# V4-AddOnSduino-V02-008.net
KiCad netlist of a schematic drawn in EAGLE
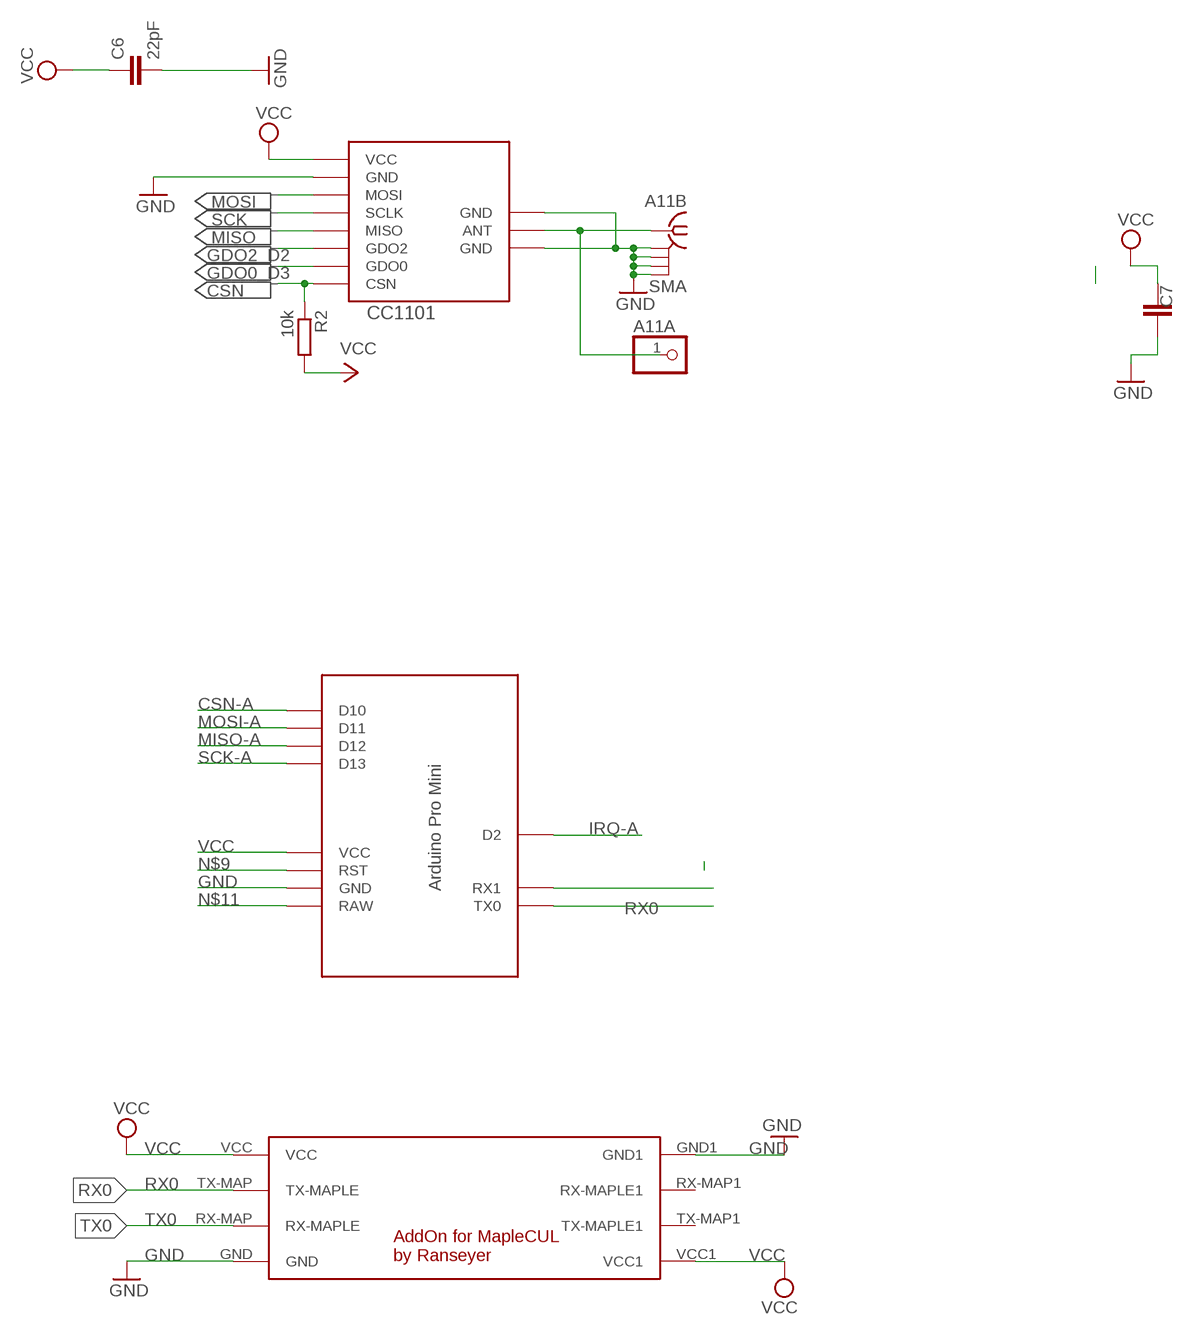
[diagram p0: schematic, sheet 1]

(export (version "E")
  (design (tool "Eeschema 10.0.6"))
  (components
    (comp (ref "A11A")
      (value "PINHD-1X1")
      (footprint "eagle-import:1X01")
      (libsource (lib "eagle-import") (part "PINHD-1X1"))
    )
    (comp (ref "A11B")
      (value "SMA")
      (footprint "eagle-import:SMA")
      (libsource (lib "eagle-import") (part "SMA"))
    )
    (comp (ref "C6")
      (value "22pF")
      (footprint "eagle-import:C0805")
      (libsource (lib "eagle-import") (part "C-EUC0805"))
    )
    (comp (ref "C7")
      (value "C-EUC1812")
      (footprint "eagle-import:C1812")
      (libsource (lib "eagle-import") (part "C-EUC1812"))
    )
    (comp (ref "CC1101")
      (value "CC1101_MODULE1SMD")
      (footprint "eagle-import:CC1101_MODULE1_SMD")
      (libsource (lib "eagle-import") (part "CC1101_MODULE1SMD"))
    )
    (comp (ref "R2")
      (value "10k")
      (footprint "eagle-import:M0805")
      (libsource (lib "eagle-import") (part "R-EU_M0805"))
    )
    (comp (ref "U$1")
      (value "MARTIN-PROMINI-SPI")
      (footprint "eagle-import:MARTIN-PRO-SPI")
      (libsource (lib "eagle-import") (part "MARTIN-PROMINI-SPI"))
    )
    (comp (ref "U$2")
      (value "MAPLE-CUL-ADDON-V01")
      (footprint "eagle-import:MAPLE-CUL-V01")
      (libsource (lib "eagle-import") (part "MAPLE-CUL-ADDON-V01"))
    )
  )
  (nets
    (net (code "1") (name "/CSN") (class "Default")
      (node (ref "CC1101") (pin "CSN") (pinfunction "CSN_CSN") (pintype "bidirectional"))
      (node (ref "R2") (pin "1") (pinfunction "1_1") (pintype "passive"))
    )
    (net (code "2") (name "/CSN-A") (class "Default")
      (node (ref "U$1") (pin "D10") (pinfunction "D10_D10") (pintype "bidirectional"))
    )
    (net (code "3") (name "/GDO0_D3") (class "Default")
      (node (ref "CC1101") (pin "GDO0") (pinfunction "GDO0_GDO0") (pintype "bidirectional"))
    )
    (net (code "4") (name "/GDO2_D2") (class "Default")
      (node (ref "CC1101") (pin "GDO2") (pinfunction "GDO2_GDO2") (pintype "bidirectional"))
    )
    (net (code "5") (name "/IRQ-A") (class "Default")
      (node (ref "U$1") (pin "D2") (pinfunction "D2_D2") (pintype "bidirectional"))
    )
    (net (code "6") (name "/MISO") (class "Default")
      (node (ref "CC1101") (pin "MISO") (pinfunction "MISO_MISO") (pintype "bidirectional"))
    )
    (net (code "7") (name "/MISO-A") (class "Default")
      (node (ref "U$1") (pin "D12") (pinfunction "D12_D12") (pintype "bidirectional"))
    )
    (net (code "8") (name "/MOSI") (class "Default")
      (node (ref "CC1101") (pin "MOSI") (pinfunction "MOSI_MOSI") (pintype "bidirectional"))
    )
    (net (code "9") (name "/MOSI-A") (class "Default")
      (node (ref "U$1") (pin "D11") (pinfunction "D11_D11") (pintype "bidirectional"))
    )
    (net (code "10") (name "/N$9") (class "Default")
      (node (ref "U$1") (pin "RST") (pinfunction "RST_RST") (pintype "bidirectional"))
    )
    (net (code "11") (name "/N$11") (class "Default")
      (node (ref "U$1") (pin "RAW") (pinfunction "RAW_RAW") (pintype "bidirectional"))
    )
    (net (code "12") (name "/SCK") (class "Default")
      (node (ref "CC1101") (pin "SCLK") (pinfunction "SCLK_SCLK") (pintype "bidirectional"))
    )
    (net (code "13") (name "/SCK-A") (class "Default")
      (node (ref "U$1") (pin "D13") (pinfunction "D13_D13") (pintype "bidirectional"))
    )
    (net (code "14") (name "GND") (class "Default")
      (node (ref "A11B") (pin "GND@1") (pinfunction "2_GND@1") (pintype "passive"))
      (node (ref "A11B") (pin "GND@2") (pinfunction "3_GND@2") (pintype "passive"))
      (node (ref "A11B") (pin "GND@3") (pinfunction "4_GND@3") (pintype "passive"))
      (node (ref "A11B") (pin "GND@4") (pinfunction "5_GND@4") (pintype "passive"))
      (node (ref "C6") (pin "2") (pinfunction "2_2") (pintype "passive"))
      (node (ref "C7") (pin "1") (pinfunction "1_1") (pintype "passive"))
      (node (ref "CC1101") (pin "GND@0") (pinfunction "GND_GND@0") (pintype "power_in"))
      (node (ref "CC1101") (pin "GND@1") (pinfunction "GND_GND@1") (pintype "power_in"))
      (node (ref "CC1101") (pin "GND@2") (pinfunction "GND_GND@2") (pintype "power_in"))
      (node (ref "U$1") (pin "GND") (pinfunction "GND_GND") (pintype "bidirectional"))
      (node (ref "U$2") (pin "GND") (pinfunction "GND_GND") (pintype "bidirectional"))
      (node (ref "U$2") (pin "GND1") (pinfunction "GND1_GND1") (pintype "bidirectional"))
    )
    (net (code "15") (name "Net-(A11A-Pad1)") (class "Default")
      (node (ref "A11A") (pin "1") (pinfunction "1_1") (pintype "passive"))
      (node (ref "A11B") (pin "1") (pinfunction "1_1") (pintype "passive"))
      (node (ref "CC1101") (pin "ANT") (pinfunction "ANT_ANT") (pintype "output"))
    )
    (net (code "16") (name "RX0") (class "Default")
      (node (ref "U$1") (pin "TX0") (pinfunction "TX0_TX0") (pintype "bidirectional"))
      (node (ref "U$2") (pin "TX-MAP") (pinfunction "TX-MAPLE_TX-MAP") (pintype "bidirectional"))
    )
    (net (code "17") (name "TX0") (class "Default")
      (node (ref "U$1") (pin "RX1") (pinfunction "RX1_RX1") (pintype "bidirectional"))
      (node (ref "U$2") (pin "RX-MAP") (pinfunction "RX-MAPLE_RX-MAP") (pintype "bidirectional"))
    )
    (net (code "18") (name "VCC") (class "Default")
      (node (ref "C6") (pin "1") (pinfunction "1_1") (pintype "passive"))
      (node (ref "C7") (pin "2") (pinfunction "2_2") (pintype "passive"))
      (node (ref "CC1101") (pin "VCC") (pinfunction "VCC_VCC") (pintype "power_in"))
      (node (ref "R2") (pin "2") (pinfunction "2_2") (pintype "passive"))
      (node (ref "U$1") (pin "VCC") (pinfunction "VCC_VCC") (pintype "bidirectional"))
      (node (ref "U$2") (pin "VCC") (pinfunction "VCC_VCC") (pintype "bidirectional"))
      (node (ref "U$2") (pin "VCC1") (pinfunction "VCC1_VCC1") (pintype "bidirectional"))
    )
    (net (code "19") (name "unconnected-(U$2-RX-MAPLE1-PadRX-MAP1)") (class "Default")
      (node (ref "U$2") (pin "RX-MAP1") (pinfunction "RX-MAPLE1_RX-MAP1") (pintype "bidirectional"))
    )
    (net (code "20") (name "unconnected-(U$2-TX-MAPLE1-PadTX-MAP1)") (class "Default")
      (node (ref "U$2") (pin "TX-MAP1") (pinfunction "TX-MAPLE1_TX-MAP1") (pintype "bidirectional"))
    )
  )
)
